# urbieBoard.net
KiCad netlist of a schematic drawn in EAGLE
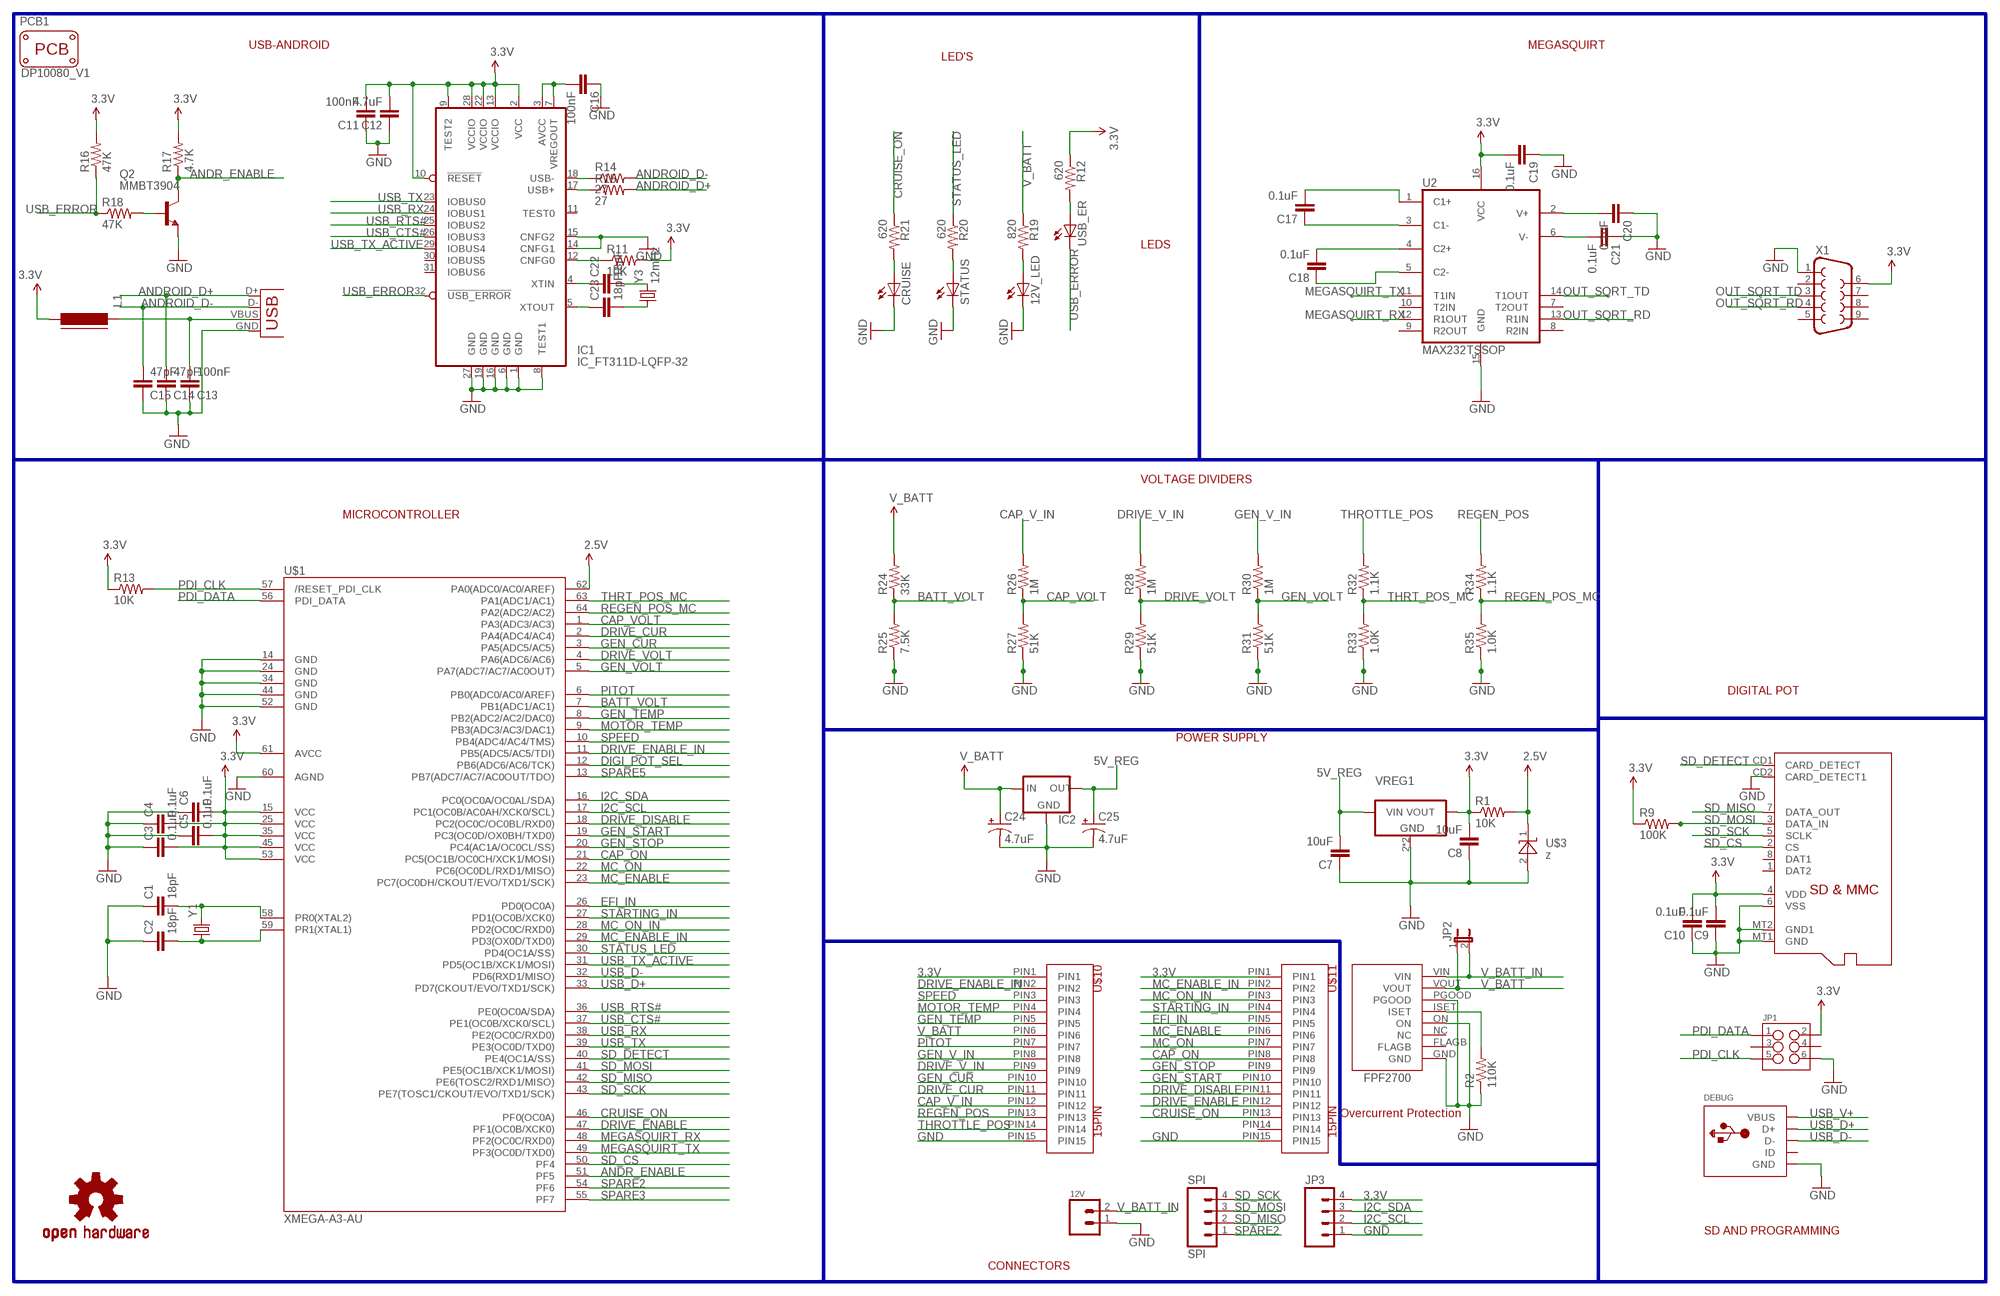
[diagram p0: schematic, sheet 1]

(export (version "E")
  (design (tool "Eeschema 10.0.6"))
  (components
    (comp (ref "12V")
      (value "DURACLIK-2SMD")
      (footprint "eagle-import:DURACLIK-2")
      (libsource (lib "eagle-import") (part "DURACLIK-2SMD"))
    )
    (comp (ref "12V_LED")
      (value "LEDCHIP-LED0603")
      (footprint "eagle-import:CHIP-LED0603")
      (libsource (lib "eagle-import") (part "LEDCHIP-LED0603"))
    )
    (comp (ref "C1")
      (value "18pF")
      (footprint "eagle-import:0603-CAP")
      (fields (field (name "MPN") "06031A180JAT2A"))
      (libsource (lib "eagle-import") (part "CAP0603-CAP"))
    )
    (comp (ref "C2")
      (value "18pF")
      (footprint "eagle-import:0603-CAP")
      (fields (field (name "MPN") "06031A180JAT2A"))
      (libsource (lib "eagle-import") (part "CAP0603-CAP"))
    )
    (comp (ref "C3")
      (value "0.1uF")
      (footprint "eagle-import:0603-CAP")
      (libsource (lib "eagle-import") (part "CAP0603-CAP"))
    )
    (comp (ref "C4")
      (value "0.1uF")
      (footprint "eagle-import:0603-CAP")
      (libsource (lib "eagle-import") (part "CAP0603-CAP"))
    )
    (comp (ref "C5")
      (value "0.1uF")
      (footprint "eagle-import:0603-CAP")
      (libsource (lib "eagle-import") (part "CAP0603-CAP"))
    )
    (comp (ref "C6")
      (value "0.1uF")
      (footprint "eagle-import:0603-CAP")
      (libsource (lib "eagle-import") (part "CAP0603-CAP"))
    )
    (comp (ref "C7")
      (value "10uF")
      (footprint "eagle-import:0603-CAP")
      (libsource (lib "eagle-import") (part "CAP0603-CAP"))
    )
    (comp (ref "C8")
      (value "10uF")
      (footprint "eagle-import:0603-CAP")
      (libsource (lib "eagle-import") (part "CAP0603-CAP"))
    )
    (comp (ref "C9")
      (value "0.1uF")
      (footprint "eagle-import:0603-CAP")
      (libsource (lib "eagle-import") (part "CAP0603-CAP"))
    )
    (comp (ref "C10")
      (value "0.1uF")
      (footprint "eagle-import:0603-CAP")
      (libsource (lib "eagle-import") (part "CAP0603-CAP"))
    )
    (comp (ref "C11")
      (value "100nF")
      (footprint "eagle-import:0603-CAP")
      (libsource (lib "eagle-import") (part "CAP0603-CAP"))
    )
    (comp (ref "C12")
      (value "4.7uF")
      (footprint "eagle-import:0603-CAP")
      (libsource (lib "eagle-import") (part "CAP0603-CAP"))
    )
    (comp (ref "C13")
      (value "100nF")
      (footprint "eagle-import:0603-CAP")
      (libsource (lib "eagle-import") (part "CAP0603-CAP"))
    )
    (comp (ref "C14")
      (value "47pF")
      (footprint "eagle-import:0603-CAP")
      (libsource (lib "eagle-import") (part "CAP0603-CAP"))
    )
    (comp (ref "C15")
      (value "47pF")
      (footprint "eagle-import:0603-CAP")
      (libsource (lib "eagle-import") (part "CAP0603-CAP"))
    )
    (comp (ref "C16")
      (value "100nF")
      (footprint "eagle-import:0603-CAP")
      (libsource (lib "eagle-import") (part "CAP0603-CAP"))
    )
    (comp (ref "C17")
      (value "0.1uF")
      (footprint "eagle-import:0603-CAP")
      (libsource (lib "eagle-import") (part "CAP0603-CAP"))
    )
    (comp (ref "C18")
      (value "0.1uF")
      (footprint "eagle-import:0603-CAP")
      (libsource (lib "eagle-import") (part "CAP0603-CAP"))
    )
    (comp (ref "C19")
      (value "0.1uF")
      (footprint "eagle-import:0603-CAP")
      (libsource (lib "eagle-import") (part "CAP0603-CAP"))
    )
    (comp (ref "C20")
      (value "0.1uF")
      (footprint "eagle-import:0603-CAP")
      (libsource (lib "eagle-import") (part "CAP0603-CAP"))
    )
    (comp (ref "C21")
      (value "0.1uF")
      (footprint "eagle-import:0603-CAP")
      (libsource (lib "eagle-import") (part "CAP0603-CAP"))
    )
    (comp (ref "C22")
      (value "18pF")
      (footprint "eagle-import:0603-CAP")
      (fields (field (name "MPN") "06031A180JAT2A"))
      (libsource (lib "eagle-import") (part "CAP0603-CAP"))
    )
    (comp (ref "C23")
      (value "18pF")
      (footprint "eagle-import:0603-CAP")
      (fields (field (name "MPN") "06031A180JAT2A"))
      (libsource (lib "eagle-import") (part "CAP0603-CAP"))
    )
    (comp (ref "C24")
      (value "4.7uF")
      (footprint "eagle-import:CPOL-RADIAL-10UF-25V")
      (libsource (lib "eagle-import") (part "CAP_POLPTH2"))
    )
    (comp (ref "C25")
      (value "4.7uF")
      (footprint "eagle-import:CPOL-RADIAL-10UF-25V")
      (libsource (lib "eagle-import") (part "CAP_POLPTH2"))
    )
    (comp (ref "CRUISE")
      (value "LEDCHIP-LED0603")
      (footprint "eagle-import:CHIP-LED0603")
      (libsource (lib "eagle-import") (part "LEDCHIP-LED0603"))
    )
    (comp (ref "DEBUG")
      (value "USBMINIB")
      (footprint "eagle-import:USB-MINIB")
      (libsource (lib "eagle-import") (part "USBMINIB"))
    )
    (comp (ref "IC1")
      (value "IC_FT311D-LQFP-32")
      (footprint "eagle-import:LQFP-32")
      (libsource (lib "eagle-import") (part "IC_FT311D-LQFP-32"))
    )
    (comp (ref "IC2")
      (value "V_REG_78XXSINK")
      (footprint "eagle-import:TO220-IGO")
      (libsource (lib "eagle-import") (part "V_REG_78XXSINK"))
    )
    (comp (ref "JP1")
      (value "M03X22X3_SILK_SM")
      (footprint "eagle-import:2X3")
      (libsource (lib "eagle-import") (part "M03X22X3_SILK_SM"))
    )
    (comp (ref "JP2")
      (value "JP1E")
      (footprint "eagle-import:JP1")
      (libsource (lib "eagle-import") (part "JP1E"))
    )
    (comp (ref "JP3")
      (value "M04POLAR_LOCK")
      (footprint "eagle-import:MOLEX-1X4_LOCK")
      (libsource (lib "eagle-import") (part "M04POLAR_LOCK"))
    )
    (comp (ref "JP4")
      (value "USB-A-S")
      (footprint "eagle-import:USB-A-S")
      (libsource (lib "eagle-import") (part "USB-A-S"))
    )
    (comp (ref "L1")
      (value "FERRITE-0805")
      (footprint "eagle-import:FB805")
      (libsource (lib "eagle-import") (part "FERRITE-0805"))
    )
    (comp (ref "LOGO1")
      (value "OSHW-LOGOM")
      (footprint "eagle-import:OSHW-LOGO-M")
      (libsource (lib "eagle-import") (part "OSHW-LOGOM"))
    )
    (comp (ref "PCB1")
      (value "PCB_DP_RECTANGLE-80X100")
      (footprint "eagle-import:DP10080_V1")
      (libsource (lib "eagle-import") (part "PCB_DP_RECTANGLE-80X100"))
    )
    (comp (ref "Q2")
      (value "MMBT3904")
      (footprint "eagle-import:SOT23-BEC")
      (libsource (lib "eagle-import") (part "BCX20SMD"))
    )
    (comp (ref "R1")
      (value "10K")
      (footprint "eagle-import:0603-RES")
      (libsource (lib "eagle-import") (part "RESISTOR0603-RES"))
    )
    (comp (ref "R2")
      (value "110K")
      (footprint "eagle-import:0603-RES")
      (libsource (lib "eagle-import") (part "RESISTOR0603-RES"))
    )
    (comp (ref "R9")
      (value "100K")
      (footprint "eagle-import:0603-RES")
      (libsource (lib "eagle-import") (part "RESISTOR0603-RES"))
    )
    (comp (ref "R11")
      (value "10K")
      (footprint "eagle-import:0603-RES")
      (libsource (lib "eagle-import") (part "RESISTOR0603-RES"))
    )
    (comp (ref "R12")
      (value "620")
      (footprint "eagle-import:0603-RES")
      (libsource (lib "eagle-import") (part "RESISTOR0603-RES"))
    )
    (comp (ref "R13")
      (value "10K")
      (footprint "eagle-import:0603-RES")
      (libsource (lib "eagle-import") (part "RESISTOR0603-RES"))
    )
    (comp (ref "R14")
      (value "27")
      (footprint "eagle-import:0603-RES")
      (libsource (lib "eagle-import") (part "RESISTOR0603-RES"))
    )
    (comp (ref "R15")
      (value "27")
      (footprint "eagle-import:0603-RES")
      (libsource (lib "eagle-import") (part "RESISTOR0603-RES"))
    )
    (comp (ref "R16")
      (value "47K")
      (footprint "eagle-import:0603-RES")
      (libsource (lib "eagle-import") (part "RESISTOR0603-RES"))
    )
    (comp (ref "R17")
      (value "4.7K")
      (footprint "eagle-import:0603-RES")
      (libsource (lib "eagle-import") (part "RESISTOR0603-RES"))
    )
    (comp (ref "R18")
      (value "47K")
      (footprint "eagle-import:0603-RES")
      (libsource (lib "eagle-import") (part "RESISTOR0603-RES"))
    )
    (comp (ref "R19")
      (value "820")
      (footprint "eagle-import:0603-RES")
      (libsource (lib "eagle-import") (part "RESISTOR0603-RES"))
    )
    (comp (ref "R20")
      (value "620")
      (footprint "eagle-import:0603-RES")
      (libsource (lib "eagle-import") (part "RESISTOR0603-RES"))
    )
    (comp (ref "R21")
      (value "620")
      (footprint "eagle-import:0603-RES")
      (libsource (lib "eagle-import") (part "RESISTOR0603-RES"))
    )
    (comp (ref "R24")
      (value "33K")
      (footprint "eagle-import:0603-RES")
      (libsource (lib "eagle-import") (part "RESISTOR0603-RES"))
    )
    (comp (ref "R25")
      (value "7.5K")
      (footprint "eagle-import:0603-RES")
      (libsource (lib "eagle-import") (part "RESISTOR0603-RES"))
    )
    (comp (ref "R26")
      (value "1M")
      (footprint "eagle-import:0603-RES")
      (libsource (lib "eagle-import") (part "RESISTOR0603-RES"))
    )
    (comp (ref "R27")
      (value "51K")
      (footprint "eagle-import:0603-RES")
      (libsource (lib "eagle-import") (part "RESISTOR0603-RES"))
    )
    (comp (ref "R28")
      (value "1M")
      (footprint "eagle-import:0603-RES")
      (libsource (lib "eagle-import") (part "RESISTOR0603-RES"))
    )
    (comp (ref "R29")
      (value "51K")
      (footprint "eagle-import:0603-RES")
      (libsource (lib "eagle-import") (part "RESISTOR0603-RES"))
    )
    (comp (ref "R30")
      (value "1M")
      (footprint "eagle-import:0603-RES")
      (libsource (lib "eagle-import") (part "RESISTOR0603-RES"))
    )
    (comp (ref "R31")
      (value "51K")
      (footprint "eagle-import:0603-RES")
      (libsource (lib "eagle-import") (part "RESISTOR0603-RES"))
    )
    (comp (ref "R32")
      (value "1.1K")
      (footprint "eagle-import:0603-RES")
      (libsource (lib "eagle-import") (part "RESISTOR0603-RES"))
    )
    (comp (ref "R33")
      (value "1.0K")
      (footprint "eagle-import:0603-RES")
      (libsource (lib "eagle-import") (part "RESISTOR0603-RES"))
    )
    (comp (ref "R34")
      (value "1.1K")
      (footprint "eagle-import:0603-RES")
      (libsource (lib "eagle-import") (part "RESISTOR0603-RES"))
    )
    (comp (ref "R35")
      (value "1.0K")
      (footprint "eagle-import:0603-RES")
      (libsource (lib "eagle-import") (part "RESISTOR0603-RES"))
    )
    (comp (ref "SPI")
      (value "SPI")
      (footprint "eagle-import:MOLEX-1X4_LOCK")
      (libsource (lib "eagle-import") (part "M04POLAR_LOCK"))
    )
    (comp (ref "STATUS")
      (value "LEDCHIP-LED0603")
      (footprint "eagle-import:CHIP-LED0603")
      (libsource (lib "eagle-import") (part "LEDCHIP-LED0603"))
    )
    (comp (ref "U$1")
      (value "XMEGA-A3-AU")
      (footprint "eagle-import:TQFP64_14X14MM")
      (libsource (lib "eagle-import") (part "XMEGA-A3-AU"))
    )
    (comp (ref "U$2")
      (value "MICROSD")
      (footprint "eagle-import:MICROSD")
      (libsource (lib "eagle-import") (part "MICROSD"))
    )
    (comp (ref "U$3")
      (value "z")
      (footprint "eagle-import:SOT-23")
      (libsource (lib "eagle-import") (part "LM4040CYM3-2.5"))
    )
    (comp (ref "U$8")
      (value "FPF2700")
      (footprint "eagle-import:FPF2700")
      (libsource (lib "eagle-import") (part "FPF2700"))
    )
    (comp (ref "U$10")
      (value "15PIN")
      (footprint "eagle-import:15PIN")
      (libsource (lib "eagle-import") (part "15PIN"))
    )
    (comp (ref "U$11")
      (value "15PIN")
      (footprint "eagle-import:15PIN")
      (libsource (lib "eagle-import") (part "15PIN"))
    )
    (comp (ref "U2")
      (value "MAX232TSSOP")
      (footprint "eagle-import:TSSOP16")
      (libsource (lib "eagle-import") (part "MAX232TSSOP"))
    )
    (comp (ref "USB_ER")
      (value "LEDCHIP-LED0603")
      (footprint "eagle-import:CHIP-LED0603")
      (libsource (lib "eagle-import") (part "LEDCHIP-LED0603"))
    )
    (comp (ref "VREG1")
      (value "VREG_3PINS-SOT-223")
      (footprint "eagle-import:SOT-223")
      (libsource (lib "eagle-import") (part "VREG_3PINS-SOT-223"))
    )
    (comp (ref "X1")
      (value "DB9MALE")
      (footprint "eagle-import:DB9_MALE")
      (libsource (lib "eagle-import") (part "DB9MALE"))
    )
    (comp (ref "Y1")
      (value "CRYSTALTXC-7A")
      (footprint "eagle-import:CRYSTAL-TXC-7A")
      (libsource (lib "eagle-import") (part "CRYSTALTXC-7A"))
    )
    (comp (ref "Y3")
      (value "12mHz")
      (footprint "eagle-import:CRYSTAL-TXC-7A")
      (libsource (lib "eagle-import") (part "CRYSTALTXC-7A"))
    )
  )
  (nets
    (net (code "1") (name "/5V_REG") (class "Default")
      (node (ref "C25") (pin "1") (pinfunction "+_1") (pintype "passive"))
      (node (ref "C7") (pin "2") (pinfunction "2_2") (pintype "passive"))
      (node (ref "IC2") (pin "OUT") (pinfunction "OUT_OUT") (pintype "output"))
      (node (ref "VREG1") (pin "1") (pinfunction "VIN_1") (pintype "bidirectional"))
    )
    (net (code "2") (name "/ANDROID_D+") (class "Default")
      (node (ref "C14") (pin "2") (pinfunction "2_2") (pintype "passive"))
      (node (ref "JP4") (pin "D+") (pinfunction "D+_D+") (pintype "bidirectional"))
      (node (ref "R15") (pin "2") (pinfunction "2_2") (pintype "passive"))
    )
    (net (code "3") (name "/ANDROID_D-") (class "Default")
      (node (ref "C15") (pin "2") (pinfunction "2_2") (pintype "passive"))
      (node (ref "JP4") (pin "D-") (pinfunction "D-_D-") (pintype "bidirectional"))
      (node (ref "R14") (pin "2") (pinfunction "2_2") (pintype "passive"))
    )
    (net (code "4") (name "/ANDR_ENABLE") (class "Default")
      (node (ref "Q2") (pin "C") (pinfunction "C_C") (pintype "passive"))
      (node (ref "R17") (pin "1") (pinfunction "1_1") (pintype "passive"))
      (node (ref "U$1") (pin "51") (pinfunction "PF5_51") (pintype "bidirectional"))
    )
    (net (code "5") (name "/BATT_VOLT") (class "Default")
      (node (ref "R24") (pin "1") (pinfunction "1_1") (pintype "passive"))
      (node (ref "R25") (pin "2") (pinfunction "2_2") (pintype "passive"))
      (node (ref "U$1") (pin "7") (pinfunction "PB1(ADC1/AC1)_7") (pintype "bidirectional"))
    )
    (net (code "6") (name "/CAP_ON") (class "Default")
      (node (ref "U$1") (pin "21") (pinfunction "PC5(OC1B/OC0CH/XCK1/MOSI)_21") (pintype "bidirectional"))
      (node (ref "U$11") (pin "PIN8") (pinfunction "PIN8_PIN8") (pintype "bidirectional"))
    )
    (net (code "7") (name "/CAP_VOLT") (class "Default")
      (node (ref "R26") (pin "1") (pinfunction "1_1") (pintype "passive"))
      (node (ref "R27") (pin "2") (pinfunction "2_2") (pintype "passive"))
      (node (ref "U$1") (pin "1") (pinfunction "PA3(ADC3/AC3)_1") (pintype "bidirectional"))
    )
    (net (code "8") (name "/CAP_V_IN") (class "Default")
      (node (ref "R26") (pin "2") (pinfunction "2_2") (pintype "passive"))
      (node (ref "U$10") (pin "PIN12") (pinfunction "PIN12_PIN12") (pintype "bidirectional"))
    )
    (net (code "9") (name "/CRUISE_ON") (class "Default")
      (node (ref "R21") (pin "1") (pinfunction "1_1") (pintype "passive"))
      (node (ref "U$1") (pin "46") (pinfunction "PF0(OC0A)_46") (pintype "bidirectional"))
      (node (ref "U$11") (pin "PIN13") (pinfunction "PIN13_PIN13") (pintype "bidirectional"))
    )
    (net (code "10") (name "/DIGI_POT_SEL") (class "Default")
      (node (ref "U$1") (pin "12") (pinfunction "PB6(ADC6/AC6/TCK)_12") (pintype "bidirectional"))
    )
    (net (code "11") (name "/DRIVE_CUR") (class "Default")
      (node (ref "U$1") (pin "2") (pinfunction "PA4(ADC4/AC4)_2") (pintype "bidirectional"))
      (node (ref "U$10") (pin "PIN11") (pinfunction "PIN11_PIN11") (pintype "bidirectional"))
    )
    (net (code "12") (name "/DRIVE_DISABLE") (class "Default")
      (node (ref "U$1") (pin "18") (pinfunction "PC2(OC0C/OC0BL/RXD0)_18") (pintype "bidirectional"))
      (node (ref "U$11") (pin "PIN11") (pinfunction "PIN11_PIN11") (pintype "bidirectional"))
    )
    (net (code "13") (name "/DRIVE_ENABLE") (class "Default")
      (node (ref "U$1") (pin "47") (pinfunction "PF1(OC0B/XCK0)_47") (pintype "bidirectional"))
      (node (ref "U$11") (pin "PIN12") (pinfunction "PIN12_PIN12") (pintype "bidirectional"))
    )
    (net (code "14") (name "/DRIVE_ENABLE_IN") (class "Default")
      (node (ref "U$1") (pin "11") (pinfunction "PB5(ADC5/AC5/TDI)_11") (pintype "bidirectional"))
      (node (ref "U$10") (pin "PIN2") (pinfunction "PIN2_PIN2") (pintype "bidirectional"))
    )
    (net (code "15") (name "/DRIVE_VOLT") (class "Default")
      (node (ref "R28") (pin "1") (pinfunction "1_1") (pintype "passive"))
      (node (ref "R29") (pin "2") (pinfunction "2_2") (pintype "passive"))
      (node (ref "U$1") (pin "4") (pinfunction "PA6(ADC6/AC6)_4") (pintype "bidirectional"))
    )
    (net (code "16") (name "/DRIVE_V_IN") (class "Default")
      (node (ref "R28") (pin "2") (pinfunction "2_2") (pintype "passive"))
      (node (ref "U$10") (pin "PIN9") (pinfunction "PIN9_PIN9") (pintype "bidirectional"))
    )
    (net (code "17") (name "/EFI_IN") (class "Default")
      (node (ref "U$1") (pin "26") (pinfunction "PD0(OC0A)_26") (pintype "bidirectional"))
      (node (ref "U$11") (pin "PIN5") (pinfunction "PIN5_PIN5") (pintype "bidirectional"))
    )
    (net (code "18") (name "/GEN_CUR") (class "Default")
      (node (ref "U$1") (pin "3") (pinfunction "PA5(ADC5/AC5)_3") (pintype "bidirectional"))
      (node (ref "U$10") (pin "PIN10") (pinfunction "PIN10_PIN10") (pintype "bidirectional"))
    )
    (net (code "19") (name "/GEN_START") (class "Default")
      (node (ref "U$1") (pin "19") (pinfunction "PC3(OC0D/OX0BH/TXD0)_19") (pintype "bidirectional"))
      (node (ref "U$11") (pin "PIN10") (pinfunction "PIN10_PIN10") (pintype "bidirectional"))
    )
    (net (code "20") (name "/GEN_STOP") (class "Default")
      (node (ref "U$1") (pin "20") (pinfunction "PC4(AC1A/OC0CL/SS)_20") (pintype "bidirectional"))
      (node (ref "U$11") (pin "PIN9") (pinfunction "PIN9_PIN9") (pintype "bidirectional"))
    )
    (net (code "21") (name "/GEN_TEMP") (class "Default")
      (node (ref "U$1") (pin "8") (pinfunction "PB2(ADC2/AC2/DAC0)_8") (pintype "bidirectional"))
      (node (ref "U$10") (pin "PIN5") (pinfunction "PIN5_PIN5") (pintype "bidirectional"))
    )
    (net (code "22") (name "/GEN_VOLT") (class "Default")
      (node (ref "R30") (pin "1") (pinfunction "1_1") (pintype "passive"))
      (node (ref "R31") (pin "2") (pinfunction "2_2") (pintype "passive"))
      (node (ref "U$1") (pin "5") (pinfunction "PA7(ADC7/AC7/AC0OUT)_5") (pintype "bidirectional"))
    )
    (net (code "23") (name "/GEN_V_IN") (class "Default")
      (node (ref "R30") (pin "2") (pinfunction "2_2") (pintype "passive"))
      (node (ref "U$10") (pin "PIN8") (pinfunction "PIN8_PIN8") (pintype "bidirectional"))
    )
    (net (code "24") (name "/I2C_SCL") (class "Default")
      (node (ref "JP3") (pin "2") (pinfunction "2_2") (pintype "passive"))
      (node (ref "U$1") (pin "17") (pinfunction "PC1(OC0B/AC0AH/XCK0/SCL)_17") (pintype "bidirectional"))
    )
    (net (code "25") (name "/I2C_SDA") (class "Default")
      (node (ref "JP3") (pin "3") (pinfunction "3_3") (pintype "passive"))
      (node (ref "U$1") (pin "16") (pinfunction "PC0(OC0A/OC0AL/SDA)_16") (pintype "bidirectional"))
    )
    (net (code "26") (name "/MC_ENABLE") (class "Default")
      (node (ref "U$1") (pin "23") (pinfunction "PC7(OC0DH/CKOUT/EVO/TXD1/SCK)_23") (pintype "bidirectional"))
      (node (ref "U$11") (pin "PIN6") (pinfunction "PIN6_PIN6") (pintype "bidirectional"))
    )
    (net (code "27") (name "/MC_ENABLE_IN") (class "Default")
      (node (ref "U$1") (pin "29") (pinfunction "PD3(OX0D/TXD0)_29") (pintype "bidirectional"))
      (node (ref "U$11") (pin "PIN2") (pinfunction "PIN2_PIN2") (pintype "bidirectional"))
    )
    (net (code "28") (name "/MC_ON") (class "Default")
      (node (ref "U$1") (pin "22") (pinfunction "PC6(OC0DL/RXD1/MISO)_22") (pintype "bidirectional"))
      (node (ref "U$11") (pin "PIN7") (pinfunction "PIN7_PIN7") (pintype "bidirectional"))
    )
    (net (code "29") (name "/MC_ON_IN") (class "Default")
      (node (ref "U$1") (pin "28") (pinfunction "PD2(OC0C/RXD0)_28") (pintype "bidirectional"))
      (node (ref "U$11") (pin "PIN3") (pinfunction "PIN3_PIN3") (pintype "bidirectional"))
    )
    (net (code "30") (name "/MEGASQUIRT_RX") (class "Default")
      (node (ref "U$1") (pin "48") (pinfunction "PF2(OC0C/RXD0)_48") (pintype "bidirectional"))
      (node (ref "U2") (pin "12") (pinfunction "R1OUT_12") (pintype "output"))
    )
    (net (code "31") (name "/MEGASQUIRT_TX") (class "Default")
      (node (ref "U$1") (pin "49") (pinfunction "PF3(OC0D/TXD0)_49") (pintype "bidirectional"))
      (node (ref "U2") (pin "11") (pinfunction "T1IN_11") (pintype "input"))
    )
    (net (code "32") (name "/MOTOR_TEMP") (class "Default")
      (node (ref "U$1") (pin "9") (pinfunction "PB3(ADC3/AC3/DAC1)_9") (pintype "bidirectional"))
      (node (ref "U$10") (pin "PIN4") (pinfunction "PIN4_PIN4") (pintype "bidirectional"))
    )
    (net (code "33") (name "/OUT_SQRT_RD") (class "Default")
      (node (ref "U2") (pin "13") (pinfunction "R1IN_13") (pintype "input"))
      (node (ref "X1") (pin "4") (pinfunction "4_4") (pintype "passive"))
    )
    (net (code "34") (name "/OUT_SQRT_TD") (class "Default")
      (node (ref "U2") (pin "14") (pinfunction "T1OUT_14") (pintype "output"))
      (node (ref "X1") (pin "3") (pinfunction "3_3") (pintype "passive"))
    )
    (net (code "35") (name "/PDI_CLK") (class "Default")
      (node (ref "JP1") (pin "5") (pinfunction "5_5") (pintype "bidirectional"))
      (node (ref "R13") (pin "2") (pinfunction "2_2") (pintype "passive"))
      (node (ref "U$1") (pin "57") (pinfunction "/RESET_PDI_CLK_57") (pintype "bidirectional"))
    )
    (net (code "36") (name "/PDI_DATA") (class "Default")
      (node (ref "JP1") (pin "1") (pinfunction "1_1") (pintype "bidirectional"))
      (node (ref "U$1") (pin "56") (pinfunction "PDI_DATA_56") (pintype "bidirectional"))
    )
    (net (code "37") (name "/PITOT") (class "Default")
      (node (ref "U$1") (pin "6") (pinfunction "PB0(ADC0/AC0/AREF)_6") (pintype "bidirectional"))
      (node (ref "U$10") (pin "PIN7") (pinfunction "PIN7_PIN7") (pintype "bidirectional"))
    )
    (net (code "38") (name "/REGEN_POS") (class "Default")
      (node (ref "R34") (pin "2") (pinfunction "2_2") (pintype "passive"))
      (node (ref "U$10") (pin "PIN13") (pinfunction "PIN13_PIN13") (pintype "bidirectional"))
    )
    (net (code "39") (name "/REGEN_POS_MC") (class "Default")
      (node (ref "R34") (pin "1") (pinfunction "1_1") (pintype "passive"))
      (node (ref "R35") (pin "2") (pinfunction "2_2") (pintype "passive"))
      (node (ref "U$1") (pin "64") (pinfunction "PA2(ADC2/AC2)_64") (pintype "bidirectional"))
    )
    (net (code "40") (name "/SD_CS") (class "Default")
      (node (ref "U$1") (pin "50") (pinfunction "PF4_50") (pintype "bidirectional"))
      (node (ref "U$2") (pin "2") (pinfunction "CS_2") (pintype "input"))
    )
    (net (code "41") (name "/SD_DETECT") (class "Default")
      (node (ref "U$1") (pin "40") (pinfunction "PE4(OC1A/SS)_40") (pintype "bidirectional"))
      (node (ref "U$2") (pin "CD1") (pinfunction "CARD_DETECT_CD1") (pintype "passive"))
    )
    (net (code "42") (name "/SD_MISO") (class "Default")
      (node (ref "SPI") (pin "2") (pinfunction "2_2") (pintype "passive"))
      (node (ref "U$1") (pin "42") (pinfunction "PE6(TOSC2/RXD1/MISO)_42") (pintype "bidirectional"))
      (node (ref "U$2") (pin "7") (pinfunction "DATA_OUT_7") (pintype "output"))
    )
    (net (code "43") (name "/SD_MOSI") (class "Default")
      (node (ref "R9") (pin "2") (pinfunction "2_2") (pintype "passive"))
      (node (ref "SPI") (pin "3") (pinfunction "3_3") (pintype "passive"))
      (node (ref "U$1") (pin "41") (pinfunction "PE5(OC1B/XCK1/MOSI)_41") (pintype "bidirectional"))
      (node (ref "U$2") (pin "3") (pinfunction "DATA_IN_3") (pintype "input"))
    )
    (net (code "44") (name "/SD_SCK") (class "Default")
      (node (ref "SPI") (pin "4") (pinfunction "4_4") (pintype "passive"))
      (node (ref "U$1") (pin "43") (pinfunction "PE7(TOSC1/CKOUT/EVO/TXD1/SCK)_43") (pintype "bidirectional"))
      (node (ref "U$2") (pin "5") (pinfunction "SCLK_5") (pintype "input"))
    )
    (net (code "45") (name "/SPARE2") (class "Default")
      (node (ref "SPI") (pin "1") (pinfunction "1_1") (pintype "passive"))
      (node (ref "U$1") (pin "54") (pinfunction "PF6_54") (pintype "bidirectional"))
    )
    (net (code "46") (name "/SPARE3") (class "Default")
      (node (ref "U$1") (pin "55") (pinfunction "PF7_55") (pintype "bidirectional"))
    )
    (net (code "47") (name "/SPARE5") (class "Default")
      (node (ref "U$1") (pin "13") (pinfunction "PB7(ADC7/AC7/AC0OUT/TDO)_13") (pintype "bidirectional"))
    )
    (net (code "48") (name "/SPEED") (class "Default")
      (node (ref "U$1") (pin "10") (pinfunction "PB4(ADC4/AC4/TMS)_10") (pintype "bidirectional"))
      (node (ref "U$10") (pin "PIN3") (pinfunction "PIN3_PIN3") (pintype "bidirectional"))
    )
    (net (code "49") (name "/STARTING_IN") (class "Default")
      (node (ref "U$1") (pin "27") (pinfunction "PD1(OC0B/XCK0)_27") (pintype "bidirectional"))
      (node (ref "U$11") (pin "PIN4") (pinfunction "PIN4_PIN4") (pintype "bidirectional"))
    )
    (net (code "50") (name "/STATUS_LED") (class "Default")
      (node (ref "R20") (pin "1") (pinfunction "1_1") (pintype "passive"))
      (node (ref "U$1") (pin "30") (pinfunction "PD4(OC1A/SS)_30") (pintype "bidirectional"))
    )
    (net (code "51") (name "/THROTTLE_POS") (class "Default")
      (node (ref "R32") (pin "2") (pinfunction "2_2") (pintype "passive"))
      (node (ref "U$10") (pin "PIN14") (pinfunction "PIN14_PIN14") (pintype "bidirectional"))
    )
    (net (code "52") (name "/THRT_POS_MC") (class "Default")
      (node (ref "R32") (pin "1") (pinfunction "1_1") (pintype "passive"))
      (node (ref "R33") (pin "2") (pinfunction "2_2") (pintype "passive"))
      (node (ref "U$1") (pin "63") (pinfunction "PA1(ADC1/AC1)_63") (pintype "bidirectional"))
    )
    (net (code "53") (name "/USB_CTS#") (class "Default")
      (node (ref "IC1") (pin "26") (pinfunction "IOBUS3_26") (pintype "bidirectional"))
      (node (ref "U$1") (pin "37") (pinfunction "PE1(OC0B/XCK0/SCL)_37") (pintype "bidirectional"))
    )
    (net (code "54") (name "/USB_D+") (class "Default")
      (node (ref "DEBUG") (pin "D+") (pinfunction "D+_D+") (pintype "bidirectional"))
      (node (ref "U$1") (pin "33") (pinfunction "PD7(CKOUT/EVO/TXD1/SCK)_33") (pintype "bidirectional"))
    )
    (net (code "55") (name "/USB_D-") (class "Default")
      (node (ref "DEBUG") (pin "D-") (pinfunction "D-_D-") (pintype "bidirectional"))
      (node (ref "U$1") (pin "32") (pinfunction "PD6(RXD1/MISO)_32") (pintype "bidirectional"))
    )
    (net (code "56") (name "/USB_ERROR") (class "Default")
      (node (ref "IC1") (pin "32") (pinfunction "~{USB_ERROR}_32") (pintype "output"))
      (node (ref "R16") (pin "1") (pinfunction "1_1") (pintype "passive"))
      (node (ref "R18") (pin "1") (pinfunction "1_1") (pintype "passive"))
      (node (ref "USB_ER") (pin "C") (pinfunction "C_C") (pintype "passive"))
    )
    (net (code "57") (name "/USB_RTS#") (class "Default")
      (node (ref "IC1") (pin "25") (pinfunction "IOBUS2_25") (pintype "bidirectional"))
      (node (ref "U$1") (pin "36") (pinfunction "PE0(OC0A/SDA)_36") (pintype "bidirectional"))
    )
    (net (code "58") (name "/USB_RX") (class "Default")
      (node (ref "IC1") (pin "24") (pinfunction "IOBUS1_24") (pintype "bidirectional"))
      (node (ref "U$1") (pin "38") (pinfunction "PE2(OC0C/RXD0)_38") (pintype "bidirectional"))
    )
    (net (code "59") (name "/USB_TX") (class "Default")
      (node (ref "IC1") (pin "23") (pinfunction "IOBUS0_23") (pintype "bidirectional"))
      (node (ref "U$1") (pin "39") (pinfunction "PE3(OC0D/TXD0)_39") (pintype "bidirectional"))
    )
    (net (code "60") (name "/USB_TX_ACTIVE") (class "Default")
      (node (ref "IC1") (pin "29") (pinfunction "IOBUS4_29") (pintype "bidirectional"))
      (node (ref "U$1") (pin "31") (pinfunction "PD5(OC1B/XCK1/MOSI)_31") (pintype "bidirectional"))
    )
    (net (code "61") (name "/USB_V+") (class "Default")
      (node (ref "DEBUG") (pin "VBUS") (pinfunction "VBUS_VBUS") (pintype "power_in"))
    )
    (net (code "62") (name "/V_BATT_IN") (class "Default")
      (node (ref "12V") (pin "2") (pinfunction "PIN2_2") (pintype "bidirectional"))
      (node (ref "JP2") (pin "2") (pinfunction "2_2") (pintype "passive"))
      (node (ref "U$8") (pin "VIN") (pinfunction "VIN_VIN") (pintype "bidirectional"))
    )
    (net (code "63") (name "2.5V") (class "Default")
      (node (ref "R1") (pin "2") (pinfunction "2_2") (pintype "passive"))
      (node (ref "U$1") (pin "62") (pinfunction "PA0(ADC0/AC0/AREF)_62") (pintype "bidirectional"))
      (node (ref "U$3") (pin "1") (pinfunction "C_1") (pintype "input"))
    )
    (net (code "64") (name "3.3V") (class "Default")
      (node (ref "C10") (pin "2") (pinfunction "2_2") (pintype "passive"))
      (node (ref "C11") (pin "2") (pinfunction "2_2") (pintype "passive"))
      (node (ref "C12") (pin "2") (pinfunction "2_2") (pintype "passive"))
      (node (ref "C19") (pin "2") (pinfunction "2_2") (pintype "passive"))
      (node (ref "C3") (pin "2") (pinfunction "2_2") (pintype "passive"))
      (node (ref "C4") (pin "2") (pinfunction "2_2") (pintype "passive"))
      (node (ref "C5") (pin "2") (pinfunction "2_2") (pintype "passive"))
      (node (ref "C6") (pin "2") (pinfunction "2_2") (pintype "passive"))
      (node (ref "C8") (pin "2") (pinfunction "2_2") (pintype "passive"))
      (node (ref "C9") (pin "2") (pinfunction "2_2") (pintype "passive"))
      (node (ref "IC1") (pin "10") (pinfunction "~{RESET}_10") (pintype "input"))
      (node (ref "IC1") (pin "13") (pinfunction "VCCIO_13") (pintype "power_in"))
      (node (ref "IC1") (pin "2") (pinfunction "VCC_2") (pintype "power_in"))
      (node (ref "IC1") (pin "22") (pinfunction "VCCIO_22") (pintype "power_in"))
      (node (ref "IC1") (pin "28") (pinfunction "VCCIO_28") (pintype "power_in"))
      (node (ref "IC1") (pin "9") (pinfunction "TEST2_9") (pintype "input"))
      (node (ref "JP1") (pin "2") (pinfunction "2_2") (pintype "bidirectional"))
      (node (ref "JP3") (pin "4") (pinfunction "4_4") (pintype "passive"))
      (node (ref "L1") (pin "2") (pinfunction "2_2") (pintype "passive"))
      (node (ref "R1") (pin "1") (pinfunction "1_1") (pintype "passive"))
      (node (ref "R11") (pin "2") (pinfunction "2_2") (pintype "passive"))
      (node (ref "R12") (pin "1") (pinfunction "1_1") (pintype "passive"))
      (node (ref "R13") (pin "1") (pinfunction "1_1") (pintype "passive"))
      (node (ref "R16") (pin "2") (pinfunction "2_2") (pintype "passive"))
      (node (ref "R17") (pin "2") (pinfunction "2_2") (pintype "passive"))
      (node (ref "R9") (pin "1") (pinfunction "1_1") (pintype "passive"))
      (node (ref "U$1") (pin "15") (pinfunction "VCC1_15") (pintype "bidirectional"))
      (node (ref "U$1") (pin "25") (pinfunction "VCC2_25") (pintype "bidirectional"))
      (node (ref "U$1") (pin "35") (pinfunction "VCC3_35") (pintype "bidirectional"))
      (node (ref "U$1") (pin "45") (pinfunction "VCC4_45") (pintype "bidirectional"))
      (node (ref "U$1") (pin "53") (pinfunction "VCC5_53") (pintype "bidirectional"))
      (node (ref "U$1") (pin "61") (pinfunction "AVCC_61") (pintype "bidirectional"))
      (node (ref "U$10") (pin "PIN1") (pinfunction "PIN1_PIN1") (pintype "bidirectional"))
      (node (ref "U$11") (pin "PIN1") (pinfunction "PIN1_PIN1") (pintype "bidirectional"))
      (node (ref "U$2") (pin "4") (pinfunction "VDD_4") (pintype "power_in"))
      (node (ref "U2") (pin "16") (pinfunction "VCC_16") (pintype "bidirectional"))
      (node (ref "VREG1") (pin "3") (pinfunction "VOUT_3") (pintype "bidirectional"))
      (node (ref "X1") (pin "6") (pinfunction "6_6") (pintype "passive"))
    )
    (net (code "65") (name "GND") (class "Default")
      (node (ref "12V") (pin "1") (pinfunction "PIN1_1") (pintype "bidirectional"))
      (node (ref "12V_LED") (pin "C") (pinfunction "C_C") (pintype "passive"))
      (node (ref "C1") (pin "1") (pinfunction "1_1") (pintype "passive"))
      (node (ref "C10") (pin "1") (pinfunction "1_1") (pintype "passive"))
      (node (ref "C11") (pin "1") (pinfunction "1_1") (pintype "passive"))
      (node (ref "C12") (pin "1") (pinfunction "1_1") (pintype "passive"))
      (node (ref "C13") (pin "1") (pinfunction "1_1") (pintype "passive"))
      (node (ref "C14") (pin "1") (pinfunction "1_1") (pintype "passive"))
      (node (ref "C15") (pin "1") (pinfunction "1_1") (pintype "passive"))
      (node (ref "C16") (pin "1") (pinfunction "1_1") (pintype "passive"))
      (node (ref "C19") (pin "1") (pinfunction "1_1") (pintype "passive"))
      (node (ref "C2") (pin "1") (pinfunction "1_1") (pintype "passive"))
      (node (ref "C20") (pin "1") (pinfunction "1_1") (pintype "passive"))
      (node (ref "C21") (pin "1") (pinfunction "1_1") (pintype "passive"))
      (node (ref "C24") (pin "2") (pinfunction "-_2") (pintype "passive"))
      (node (ref "C25") (pin "2") (pinfunction "-_2") (pintype "passive"))
      (node (ref "C3") (pin "1") (pinfunction "1_1") (pintype "passive"))
      (node (ref "C4") (pin "1") (pinfunction "1_1") (pintype "passive"))
      (node (ref "C5") (pin "1") (pinfunction "1_1") (pintype "passive"))
      (node (ref "C6") (pin "1") (pinfunction "1_1") (pintype "passive"))
      (node (ref "C7") (pin "1") (pinfunction "1_1") (pintype "passive"))
      (node (ref "C8") (pin "1") (pinfunction "1_1") (pintype "passive"))
      (node (ref "C9") (pin "1") (pinfunction "1_1") (pintype "passive"))
      (node (ref "CRUISE") (pin "C") (pinfunction "C_C") (pintype "passive"))
      (node (ref "DEBUG") (pin "GND") (pinfunction "GND_GND") (pintype "power_in"))
      (node (ref "IC1") (pin "1") (pinfunction "GND_1") (pintype "power_in"))
      (node (ref "IC1") (pin "14") (pinfunction "CNFG1_14") (pintype "input"))
      (node (ref "IC1") (pin "15") (pinfunction "CNFG2_15") (pintype "input"))
      (node (ref "IC1") (pin "16") (pinfunction "GND_16") (pintype "power_in"))
      (node (ref "IC1") (pin "19") (pinfunction "GND_19") (pintype "power_in"))
      (node (ref "IC1") (pin "27") (pinfunction "GND_27") (pintype "power_in"))
      (node (ref "IC1") (pin "6") (pinfunction "GND_6") (pintype "power_in"))
      (node (ref "IC1") (pin "8") (pinfunction "TEST1_8") (pintype "input"))
      (node (ref "IC2") (pin "GND") (pinfunction "GND_GND") (pintype "input"))
      (node (ref "JP1") (pin "6") (pinfunction "6_6") (pintype "bidirectional"))
      (node (ref "JP3") (pin "1") (pinfunction "1_1") (pintype "passive"))
      (node (ref "JP4") (pin "GND") (pinfunction "GND_GND") (pintype "bidirectional"))
      (node (ref "Q2") (pin "E") (pinfunction "E_E") (pintype "passive"))
      (node (ref "R2") (pin "1") (pinfunction "1_1") (pintype "passive"))
      (node (ref "R25") (pin "1") (pinfunction "1_1") (pintype "passive"))
      (node (ref "R27") (pin "1") (pinfunction "1_1") (pintype "passive"))
      (node (ref "R29") (pin "1") (pinfunction "1_1") (pintype "passive"))
      (node (ref "R31") (pin "1") (pinfunction "1_1") (pintype "passive"))
      (node (ref "R33") (pin "1") (pinfunction "1_1") (pintype "passive"))
      (node (ref "R35") (pin "1") (pinfunction "1_1") (pintype "passive"))
      (node (ref "STATUS") (pin "C") (pinfunction "C_C") (pintype "passive"))
      (node (ref "U$1") (pin "14") (pinfunction "GND1_14") (pintype "bidirectional"))
      (node (ref "U$1") (pin "24") (pinfunction "GND2_24") (pintype "bidirectional"))
      (node (ref "U$1") (pin "34") (pinfunction "GND3_34") (pintype "bidirectional"))
      (node (ref "U$1") (pin "44") (pinfunction "GND4_44") (pintype "bidirectional"))
      (node (ref "U$1") (pin "52") (pinfunction "GND5_52") (pintype "bidirectional"))
      (node (ref "U$1") (pin "60") (pinfunction "AGND_60") (pintype "bidirectional"))
      (node (ref "U$10") (pin "PIN15") (pinfunction "PIN15_PIN15") (pintype "bidirectional"))
      (node (ref "U$11") (pin "PIN15") (pinfunction "PIN15_PIN15") (pintype "bidirectional"))
      (node (ref "U$2") (pin "6") (pinfunction "VSS_6") (pintype "power_in"))
      (node (ref "U$2") (pin "CD2") (pinfunction "CARD_DETECT1_CD2") (pintype "passive"))
      (node (ref "U$2") (pin "MT1") (pinfunction "GND_MT1") (pintype "power_in"))
      (node (ref "U$2") (pin "MT2") (pinfunction "GND1_MT2") (pintype "power_in"))
      (node (ref "U$3") (pin "2") (pinfunction "A_2") (pintype "output"))
      (node (ref "U$8") (pin "GND") (pinfunction "GND_GND") (pintype "bidirectional"))
      (node (ref "U$8") (pin "ON") (pinfunction "ON_ON") (pintype "bidirectional"))
      (node (ref "U$8") (pin "PGOOD") (pinfunction "PGOOD_PGOOD") (pintype "bidirectional"))
      (node (ref "U2") (pin "15") (pinfunction "GND_15") (pintype "bidirectional"))
      (node (ref "VREG1") (pin "2") (pinfunction "GND_2") (pintype "bidirectional"))
      (node (ref "VREG1") (pin "4") (pinfunction "GND_4") (pintype "bidirectional"))
      (node (ref "X1") (pin "1") (pinfunction "1_1") (pintype "passive"))
    )
    (net (code "66") (name "Net-(12V_LED-PadA)") (class "Default")
      (node (ref "12V_LED") (pin "A") (pinfunction "A_A") (pintype "passive"))
      (node (ref "R19") (pin "2") (pinfunction "2_2") (pintype "passive"))
    )
    (net (code "67") (name "Net-(C13-Pad2)") (class "Default")
      (node (ref "C13") (pin "2") (pinfunction "2_2") (pintype "passive"))
      (node (ref "JP4") (pin "VBUS") (pinfunction "VBUS_VBUS") (pintype "bidirectional"))
      (node (ref "L1") (pin "1") (pinfunction "1_1") (pintype "passive"))
    )
    (net (code "68") (name "Net-(CRUISE-PadA)") (class "Default")
      (node (ref "CRUISE") (pin "A") (pinfunction "A_A") (pintype "passive"))
      (node (ref "R21") (pin "2") (pinfunction "2_2") (pintype "passive"))
    )
    (net (code "69") (name "Net-(IC1-AVCC)") (class "Default")
      (node (ref "C16") (pin "2") (pinfunction "2_2") (pintype "passive"))
      (node (ref "IC1") (pin "3") (pinfunction "AVCC_3") (pintype "power_in"))
      (node (ref "IC1") (pin "7") (pinfunction "VREGOUT_7") (pintype "power_in"))
    )
    (net (code "70") (name "Net-(IC1-CNFG0)") (class "Default")
      (node (ref "IC1") (pin "12") (pinfunction "CNFG0_12") (pintype "input"))
      (node (ref "R11") (pin "1") (pinfunction "1_1") (pintype "passive"))
    )
    (net (code "71") (name "Net-(IC1-USB+)") (class "Default")
      (node (ref "IC1") (pin "17") (pinfunction "USB+_17") (pintype "output"))
      (node (ref "R15") (pin "1") (pinfunction "1_1") (pintype "passive"))
    )
    (net (code "72") (name "Net-(IC1-USB-)") (class "Default")
      (node (ref "IC1") (pin "18") (pinfunction "USB-_18") (pintype "input"))
      (node (ref "R14") (pin "1") (pinfunction "1_1") (pintype "passive"))
    )
    (net (code "73") (name "Net-(IC1-XTIN)") (class "Default")
      (node (ref "C22") (pin "1") (pinfunction "1_1") (pintype "passive"))
      (node (ref "IC1") (pin "4") (pinfunction "XTIN_4") (pintype "input"))
    )
    (net (code "74") (name "Net-(IC1-XTOUT)") (class "Default")
      (node (ref "C23") (pin "1") (pinfunction "1_1") (pintype "passive"))
      (node (ref "IC1") (pin "5") (pinfunction "XTOUT_5") (pintype "output"))
    )
    (net (code "75") (name "Net-(Q2-PadB)") (class "Default")
      (node (ref "Q2") (pin "B") (pinfunction "B_B") (pintype "passive"))
      (node (ref "R18") (pin "2") (pinfunction "2_2") (pintype "passive"))
    )
    (net (code "76") (name "Net-(R2-Pad2)") (class "Default")
      (node (ref "R2") (pin "2") (pinfunction "2_2") (pintype "passive"))
      (node (ref "U$8") (pin "ISET") (pinfunction "ISET_ISET") (pintype "bidirectional"))
    )
    (net (code "77") (name "Net-(R12-Pad2)") (class "Default")
      (node (ref "R12") (pin "2") (pinfunction "2_2") (pintype "passive"))
      (node (ref "USB_ER") (pin "A") (pinfunction "A_A") (pintype "passive"))
    )
    (net (code "78") (name "Net-(R20-Pad2)") (class "Default")
      (node (ref "R20") (pin "2") (pinfunction "2_2") (pintype "passive"))
      (node (ref "STATUS") (pin "A") (pinfunction "A_A") (pintype "passive"))
    )
    (net (code "79") (name "Net-(U$1-PR0(XTAL2))") (class "Default")
      (node (ref "C1") (pin "2") (pinfunction "2_2") (pintype "passive"))
      (node (ref "U$1") (pin "58") (pinfunction "PR0(XTAL2)_58") (pintype "bidirectional"))
      (node (ref "Y1") (pin "P$2") (pinfunction "2_P$2") (pintype "passive"))
    )
    (net (code "80") (name "Net-(U$1-PR1(XTAL1))") (class "Default")
      (node (ref "C2") (pin "2") (pinfunction "2_2") (pintype "passive"))
      (node (ref "U$1") (pin "59") (pinfunction "PR1(XTAL1)_59") (pintype "bidirectional"))
      (node (ref "Y1") (pin "P$1") (pinfunction "1_P$1") (pintype "passive"))
    )
    (net (code "81") (name "Net-(U2-C1+)") (class "Default")
      (node (ref "C17") (pin "2") (pinfunction "2_2") (pintype "passive"))
      (node (ref "U2") (pin "1") (pinfunction "C1+_1") (pintype "bidirectional"))
    )
    (net (code "82") (name "Net-(U2-C1-)") (class "Default")
      (node (ref "C17") (pin "1") (pinfunction "1_1") (pintype "passive"))
      (node (ref "U2") (pin "3") (pinfunction "C1-_3") (pintype "bidirectional"))
    )
    (net (code "83") (name "Net-(U2-C2+)") (class "Default")
      (node (ref "C18") (pin "2") (pinfunction "2_2") (pintype "passive"))
      (node (ref "U2") (pin "4") (pinfunction "C2+_4") (pintype "bidirectional"))
    )
    (net (code "84") (name "Net-(U2-C2-)") (class "Default")
      (node (ref "C18") (pin "1") (pinfunction "1_1") (pintype "passive"))
      (node (ref "U2") (pin "5") (pinfunction "C2-_5") (pintype "bidirectional"))
    )
    (net (code "85") (name "Net-(U2-V+)") (class "Default")
      (node (ref "C20") (pin "2") (pinfunction "2_2") (pintype "passive"))
      (node (ref "U2") (pin "2") (pinfunction "V+_2") (pintype "bidirectional"))
    )
    (net (code "86") (name "Net-(U2-V-)") (class "Default")
      (node (ref "C21") (pin "2") (pinfunction "2_2") (pintype "passive"))
      (node (ref "U2") (pin "6") (pinfunction "V-_6") (pintype "bidirectional"))
    )
    (net (code "87") (name "Net-(Y3-1)") (class "Default")
      (node (ref "C23") (pin "2") (pinfunction "2_2") (pintype "passive"))
      (node (ref "Y3") (pin "P$1") (pinfunction "1_P$1") (pintype "passive"))
    )
    (net (code "88") (name "Net-(Y3-2)") (class "Default")
      (node (ref "C22") (pin "2") (pinfunction "2_2") (pintype "passive"))
      (node (ref "Y3") (pin "P$2") (pinfunction "2_P$2") (pintype "passive"))
    )
    (net (code "89") (name "V_BATT") (class "Default")
      (node (ref "C24") (pin "1") (pinfunction "+_1") (pintype "passive"))
      (node (ref "IC2") (pin "IN") (pinfunction "IN_IN") (pintype "input"))
      (node (ref "JP2") (pin "1") (pinfunction "1_1") (pintype "passive"))
      (node (ref "R19") (pin "1") (pinfunction "1_1") (pintype "passive"))
      (node (ref "R24") (pin "2") (pinfunction "2_2") (pintype "passive"))
      (node (ref "U$10") (pin "PIN6") (pinfunction "PIN6_PIN6") (pintype "bidirectional"))
      (node (ref "U$8") (pin "VOUT") (pinfunction "VOUT_VOUT") (pintype "bidirectional"))
    )
    (net (code "90") (name "unconnected-(DEBUG-PadID)") (class "Default")
      (node (ref "DEBUG") (pin "ID") (pinfunction "ID_ID") (pintype "bidirectional"))
    )
    (net (code "91") (name "unconnected-(IC1-IOBUS5-Pad30)") (class "Default")
      (node (ref "IC1") (pin "30") (pinfunction "IOBUS5_30") (pintype "bidirectional"))
    )
    (net (code "92") (name "unconnected-(IC1-IOBUS6-Pad31)") (class "Default")
      (node (ref "IC1") (pin "31") (pinfunction "IOBUS6_31") (pintype "bidirectional"))
    )
    (net (code "93") (name "unconnected-(IC1-TEST0-Pad11)") (class "Default")
      (node (ref "IC1") (pin "11") (pinfunction "TEST0_11") (pintype "output"))
    )
    (net (code "94") (name "unconnected-(JP1-Pad3)") (class "Default")
      (node (ref "JP1") (pin "3") (pinfunction "3_3") (pintype "bidirectional"))
    )
    (net (code "95") (name "unconnected-(JP1-Pad4)") (class "Default")
      (node (ref "JP1") (pin "4") (pinfunction "4_4") (pintype "bidirectional"))
    )
    (net (code "96") (name "unconnected-(U$2-DAT1-Pad8)") (class "Default")
      (node (ref "U$2") (pin "8") (pinfunction "DAT1_8") (pintype "bidirectional"))
    )
    (net (code "97") (name "unconnected-(U$2-DAT2-Pad1)") (class "Default")
      (node (ref "U$2") (pin "1") (pinfunction "DAT2_1") (pintype "bidirectional"))
    )
    (net (code "98") (name "unconnected-(U$8-PadFLAGB)") (class "Default")
      (node (ref "U$8") (pin "FLAGB") (pinfunction "FLAGB_FLAGB") (pintype "bidirectional"))
    )
    (net (code "99") (name "unconnected-(U$8-PadNC)") (class "Default")
      (node (ref "U$8") (pin "NC") (pinfunction "NC_NC") (pintype "bidirectional"))
    )
    (net (code "100") (name "unconnected-(U$11-PadPIN14)") (class "Default")
      (node (ref "U$11") (pin "PIN14") (pinfunction "PIN14_PIN14") (pintype "bidirectional"))
    )
    (net (code "101") (name "unconnected-(U2-R2IN-Pad8)") (class "Default")
      (node (ref "U2") (pin "8") (pinfunction "R2IN_8") (pintype "input"))
    )
    (net (code "102") (name "unconnected-(U2-R2OUT-Pad9)") (class "Default")
      (node (ref "U2") (pin "9") (pinfunction "R2OUT_9") (pintype "output"))
    )
    (net (code "103") (name "unconnected-(U2-T2IN-Pad10)") (class "Default")
      (node (ref "U2") (pin "10") (pinfunction "T2IN_10") (pintype "input"))
    )
    (net (code "104") (name "unconnected-(U2-T2OUT-Pad7)") (class "Default")
      (node (ref "U2") (pin "7") (pinfunction "T2OUT_7") (pintype "output"))
    )
    (net (code "105") (name "unconnected-(X1-Pad2)") (class "Default")
      (node (ref "X1") (pin "2") (pinfunction "2_2") (pintype "passive"))
    )
    (net (code "106") (name "unconnected-(X1-Pad5)") (class "Default")
      (node (ref "X1") (pin "5") (pinfunction "5_5") (pintype "passive"))
    )
    (net (code "107") (name "unconnected-(X1-Pad7)") (class "Default")
      (node (ref "X1") (pin "7") (pinfunction "7_7") (pintype "passive"))
    )
    (net (code "108") (name "unconnected-(X1-Pad8)") (class "Default")
      (node (ref "X1") (pin "8") (pinfunction "8_8") (pintype "passive"))
    )
    (net (code "109") (name "unconnected-(X1-Pad9)") (class "Default")
      (node (ref "X1") (pin "9") (pinfunction "9_9") (pintype "passive"))
    )
  )
)
